# IoTDnD.net
KiCad netlist of a schematic drawn in EAGLE
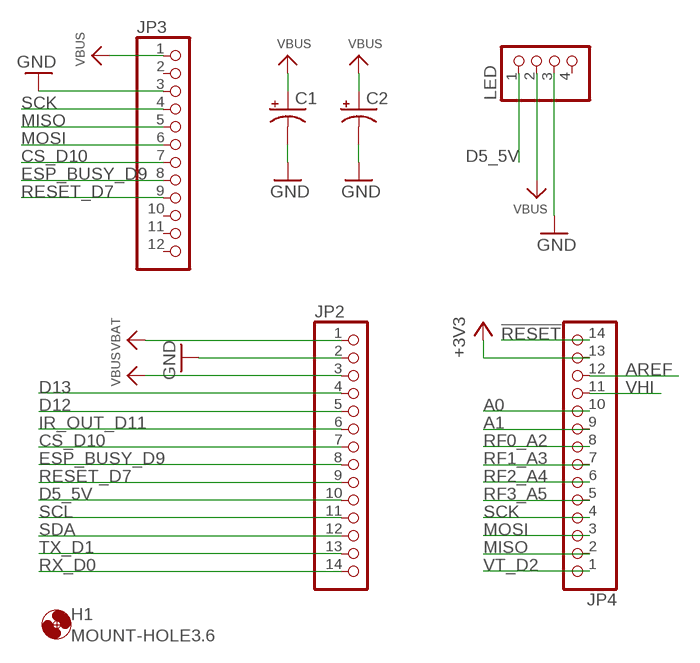
[diagram p0: schematic, sheet 1]

(export (version "E")
  (design (tool "Eeschema 10.0.6"))
  (components
    (comp (ref "C1")
      (value "CPOL-USE2.5-6")
      (footprint "eagle-import:E2,5-6")
      (libsource (lib "eagle-import") (part "CPOL-USE2.5-6"))
    )
    (comp (ref "C2")
      (value "CPOL-USE2.5-6")
      (footprint "eagle-import:E2,5-6")
      (libsource (lib "eagle-import") (part "CPOL-USE2.5-6"))
    )
    (comp (ref "H1")
      (value "MOUNT-HOLE3.6")
      (footprint "eagle-import:3,6")
      (libsource (lib "eagle-import") (part "MOUNT-HOLE3.6"))
    )
    (comp (ref "JP2")
      (value "HEADER-1X14")
      (footprint "eagle-import:1X14_ROUND70")
      (libsource (lib "eagle-import") (part "HEADER-1X14"))
    )
    (comp (ref "JP3")
      (value "HEADER-1X12")
      (footprint "eagle-import:1X12_ROUND")
      (libsource (lib "eagle-import") (part "HEADER-1X12"))
    )
    (comp (ref "JP4")
      (value "HEADER-1X14")
      (footprint "eagle-import:1X14_ROUND70")
      (libsource (lib "eagle-import") (part "HEADER-1X14"))
    )
    (comp (ref "LED")
      (value "PINHD-1X4")
      (footprint "eagle-import:1X04")
      (libsource (lib "eagle-import") (part "PINHD-1X4"))
    )
  )
  (nets
    (net (code "1") (name "+3V3") (class "Default")
      (node (ref "JP4") (pin "13") (pinfunction "13_13") (pintype "passive"))
    )
    (net (code "2") (name "/A0") (class "Default")
      (node (ref "JP4") (pin "10") (pinfunction "10_10") (pintype "passive"))
    )
    (net (code "3") (name "/A1") (class "Default")
      (node (ref "JP4") (pin "9") (pinfunction "9_9") (pintype "passive"))
    )
    (net (code "4") (name "/AREF") (class "Default")
      (node (ref "JP4") (pin "12") (pinfunction "12_12") (pintype "passive"))
    )
    (net (code "5") (name "/CS_D10") (class "Default")
      (node (ref "JP2") (pin "7") (pinfunction "7_7") (pintype "passive"))
      (node (ref "JP3") (pin "7") (pinfunction "7_7") (pintype "passive"))
    )
    (net (code "6") (name "/D5_5V") (class "Default")
      (node (ref "JP2") (pin "10") (pinfunction "10_10") (pintype "passive"))
      (node (ref "LED") (pin "1") (pinfunction "1_1") (pintype "passive"))
    )
    (net (code "7") (name "/D12") (class "Default")
      (node (ref "JP2") (pin "5") (pinfunction "5_5") (pintype "passive"))
    )
    (net (code "8") (name "/D13") (class "Default")
      (node (ref "JP2") (pin "4") (pinfunction "4_4") (pintype "passive"))
    )
    (net (code "9") (name "/ESP_BUSY_D9") (class "Default")
      (node (ref "JP2") (pin "8") (pinfunction "8_8") (pintype "passive"))
      (node (ref "JP3") (pin "8") (pinfunction "8_8") (pintype "passive"))
    )
    (net (code "10") (name "/IR_OUT_D11") (class "Default")
      (node (ref "JP2") (pin "6") (pinfunction "6_6") (pintype "passive"))
    )
    (net (code "11") (name "/MISO") (class "Default")
      (node (ref "JP3") (pin "5") (pinfunction "5_5") (pintype "passive"))
      (node (ref "JP4") (pin "2") (pinfunction "2_2") (pintype "passive"))
    )
    (net (code "12") (name "/MOSI") (class "Default")
      (node (ref "JP3") (pin "6") (pinfunction "6_6") (pintype "passive"))
      (node (ref "JP4") (pin "3") (pinfunction "3_3") (pintype "passive"))
    )
    (net (code "13") (name "/RESET_D7") (class "Default")
      (node (ref "JP2") (pin "9") (pinfunction "9_9") (pintype "passive"))
      (node (ref "JP3") (pin "9") (pinfunction "9_9") (pintype "passive"))
    )
    (net (code "14") (name "/RF0_A2") (class "Default")
      (node (ref "JP4") (pin "8") (pinfunction "8_8") (pintype "passive"))
    )
    (net (code "15") (name "/RF1_A3") (class "Default")
      (node (ref "JP4") (pin "7") (pinfunction "7_7") (pintype "passive"))
    )
    (net (code "16") (name "/RF2_A4") (class "Default")
      (node (ref "JP4") (pin "6") (pinfunction "6_6") (pintype "passive"))
    )
    (net (code "17") (name "/RF3_A5") (class "Default")
      (node (ref "JP4") (pin "5") (pinfunction "5_5") (pintype "passive"))
    )
    (net (code "18") (name "/RX_D0") (class "Default")
      (node (ref "JP2") (pin "14") (pinfunction "14_14") (pintype "passive"))
    )
    (net (code "19") (name "/SCK") (class "Default")
      (node (ref "JP3") (pin "4") (pinfunction "4_4") (pintype "passive"))
      (node (ref "JP4") (pin "4") (pinfunction "4_4") (pintype "passive"))
    )
    (net (code "20") (name "/SCL") (class "Default")
      (node (ref "JP2") (pin "11") (pinfunction "11_11") (pintype "passive"))
    )
    (net (code "21") (name "/SDA") (class "Default")
      (node (ref "JP2") (pin "12") (pinfunction "12_12") (pintype "passive"))
    )
    (net (code "22") (name "/TX_D1") (class "Default")
      (node (ref "JP2") (pin "13") (pinfunction "13_13") (pintype "passive"))
    )
    (net (code "23") (name "/VHI") (class "Default")
      (node (ref "JP4") (pin "11") (pinfunction "11_11") (pintype "passive"))
    )
    (net (code "24") (name "/VT_D2") (class "Default")
      (node (ref "JP4") (pin "1") (pinfunction "1_1") (pintype "passive"))
    )
    (net (code "25") (name "/~{RESET}") (class "Default")
      (node (ref "JP4") (pin "14") (pinfunction "14_14") (pintype "passive"))
    )
    (net (code "26") (name "GND") (class "Default")
      (node (ref "C1") (pin "-") (pinfunction "-_-") (pintype "passive"))
      (node (ref "C2") (pin "-") (pinfunction "-_-") (pintype "passive"))
      (node (ref "JP2") (pin "2") (pinfunction "2_2") (pintype "passive"))
      (node (ref "JP3") (pin "3") (pinfunction "3_3") (pintype "passive"))
      (node (ref "LED") (pin "3") (pinfunction "3_3") (pintype "passive"))
    )
    (net (code "27") (name "VBAT") (class "Default")
      (node (ref "JP2") (pin "1") (pinfunction "1_1") (pintype "passive"))
    )
    (net (code "28") (name "VBUS") (class "Default")
      (node (ref "C1") (pin "+") (pinfunction "+_+") (pintype "passive"))
      (node (ref "C2") (pin "+") (pinfunction "+_+") (pintype "passive"))
      (node (ref "JP2") (pin "3") (pinfunction "3_3") (pintype "passive"))
      (node (ref "JP3") (pin "1") (pinfunction "1_1") (pintype "passive"))
      (node (ref "LED") (pin "2") (pinfunction "2_2") (pintype "passive"))
    )
    (net (code "29") (name "unconnected-(JP3-Pad2)") (class "Default")
      (node (ref "JP3") (pin "2") (pinfunction "2_2") (pintype "passive"))
    )
    (net (code "30") (name "unconnected-(JP3-Pad10)") (class "Default")
      (node (ref "JP3") (pin "10") (pinfunction "10_10") (pintype "passive"))
    )
    (net (code "31") (name "unconnected-(JP3-Pad11)") (class "Default")
      (node (ref "JP3") (pin "11") (pinfunction "11_11") (pintype "passive"))
    )
    (net (code "32") (name "unconnected-(JP3-Pad12)") (class "Default")
      (node (ref "JP3") (pin "12") (pinfunction "12_12") (pintype "passive"))
    )
    (net (code "33") (name "unconnected-(LED-Pad4)") (class "Default")
      (node (ref "LED") (pin "4") (pinfunction "4_4") (pintype "passive"))
    )
  )
)
